# RB1_v2.net
KiCad netlist of a schematic drawn in EAGLE
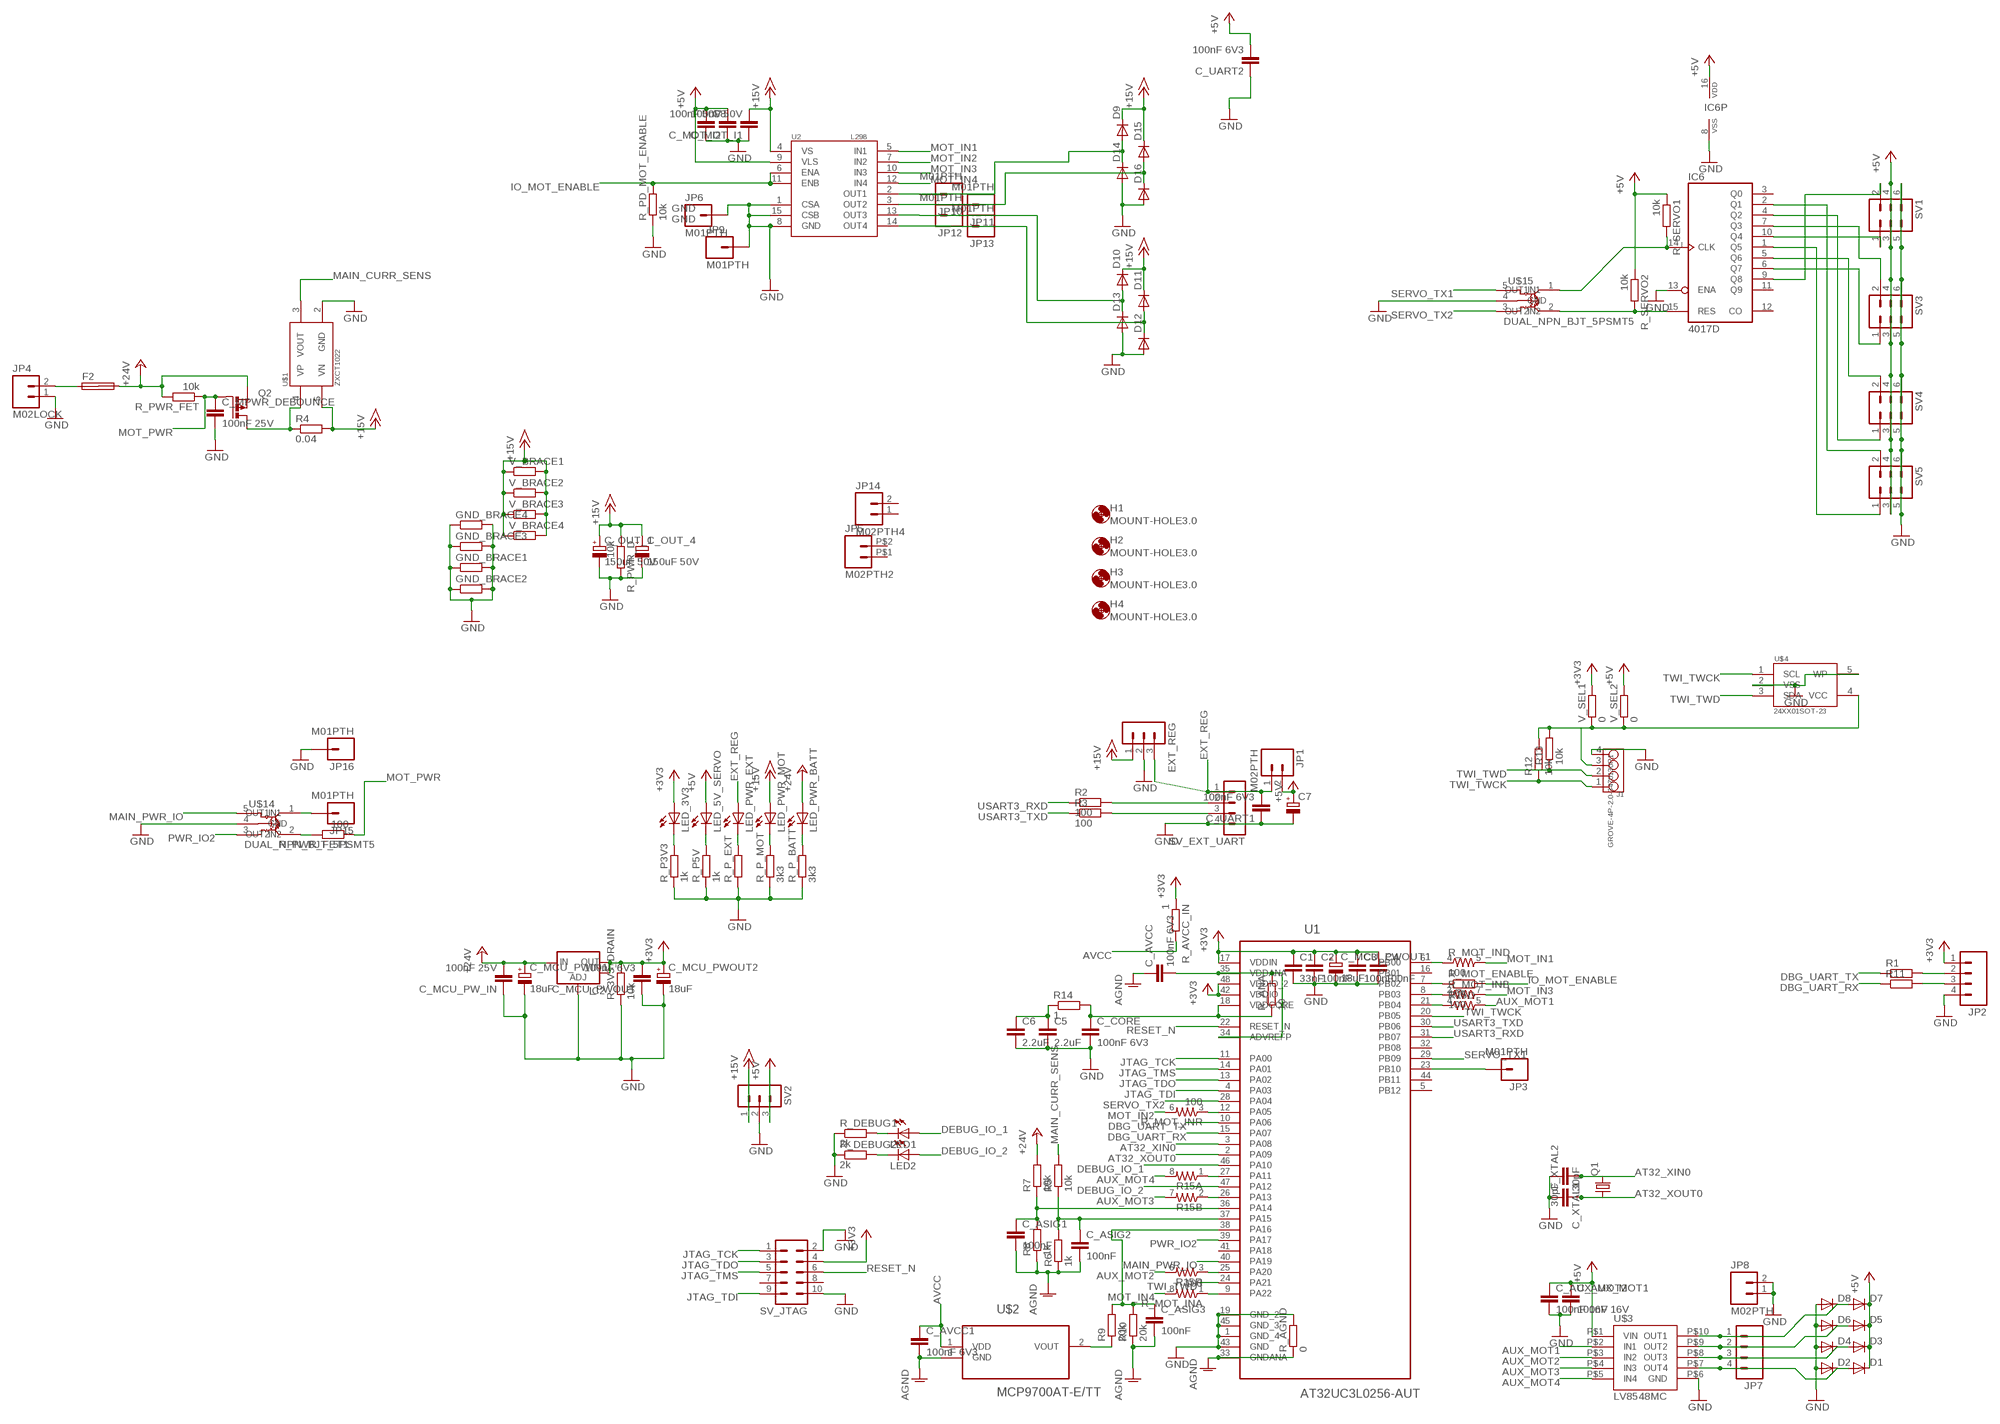
[diagram p0: schematic, sheet 1]

(export (version "E")
  (design (tool "Eeschema 10.0.6"))
  (components
    (comp (ref "C1")
      (value "33nF")
      (footprint "eagle-import:C0603K")
      (libsource (lib "eagle-import") (part "C-EUC0603K"))
    )
    (comp (ref "C2")
      (value "100nF")
      (footprint "eagle-import:C0603K")
      (libsource (lib "eagle-import") (part "C-EUC0603K"))
    )
    (comp (ref "C3")
      (value "100nF")
      (footprint "eagle-import:C0603K")
      (libsource (lib "eagle-import") (part "C-EUC0603K"))
    )
    (comp (ref "C4")
      (value "100nF")
      (footprint "eagle-import:C0603K")
      (libsource (lib "eagle-import") (part "C-EUC0603K"))
    )
    (comp (ref "C5")
      (value "2.2uF")
      (footprint "eagle-import:C0603K")
      (libsource (lib "eagle-import") (part "C-EUC0603K"))
    )
    (comp (ref "C6")
      (value "2.2uF")
      (footprint "eagle-import:C0603K")
      (libsource (lib "eagle-import") (part "C-EUC0603K"))
    )
    (comp (ref "C7")
      (value "CPOL-EU153CLV-0807")
      (footprint "eagle-import:153CLV-0807")
      (libsource (lib "eagle-import") (part "CPOL-EU153CLV-0807"))
    )
    (comp (ref "C8")
      (value "C-EUC1210K")
      (footprint "eagle-import:C1210K")
      (libsource (lib "eagle-import") (part "C-EUC1210K"))
    )
    (comp (ref "C_ASIG1")
      (value "100nF")
      (footprint "eagle-import:C0603K")
      (libsource (lib "eagle-import") (part "C-EUC0603K"))
    )
    (comp (ref "C_ASIG2")
      (value "100nF")
      (footprint "eagle-import:C0603K")
      (libsource (lib "eagle-import") (part "C-EUC0603K"))
    )
    (comp (ref "C_ASIG3")
      (value "100nF")
      (footprint "eagle-import:C0603K")
      (libsource (lib "eagle-import") (part "C-EUC0603K"))
    )
    (comp (ref "C_AUX_MOT1")
      (value "100nF 16V")
      (footprint "eagle-import:C0603K")
      (libsource (lib "eagle-import") (part "C-EUC0603K"))
    )
    (comp (ref "C_AUX_MOT2")
      (value "100nF 16V")
      (footprint "eagle-import:C0603K")
      (libsource (lib "eagle-import") (part "C-EUC0603K"))
    )
    (comp (ref "C_AVCC")
      (value "100nF 6V3")
      (footprint "eagle-import:C0603K")
      (libsource (lib "eagle-import") (part "C-EUC0603K"))
    )
    (comp (ref "C_AVCC1")
      (value "100nF 6V3")
      (footprint "eagle-import:C0603K")
      (libsource (lib "eagle-import") (part "C-EUC0603K"))
    )
    (comp (ref "C_CORE")
      (value "100nF 6V3")
      (footprint "eagle-import:C0603K")
      (libsource (lib "eagle-import") (part "C-EUC0603K"))
    )
    (comp (ref "C_MCU_PWIN1")
      (value "18uF")
      (footprint "eagle-import:E2-5")
      (libsource (lib "eagle-import") (part "CPOL-EUE2-5"))
    )
    (comp (ref "C_MCU_PWOUT")
      (value "100nF 6V3")
      (footprint "eagle-import:C0603K")
      (libsource (lib "eagle-import") (part "C-EUC0603K"))
    )
    (comp (ref "C_MCU_PWOUT1")
      (value "18uF")
      (footprint "eagle-import:E2-5")
      (libsource (lib "eagle-import") (part "CPOL-EUE2-5"))
    )
    (comp (ref "C_MCU_PWOUT2")
      (value "18uF")
      (footprint "eagle-import:E2-5")
      (libsource (lib "eagle-import") (part "CPOL-EUE2-5"))
    )
    (comp (ref "C_MCU_PW_IN")
      (value "100nF 25V")
      (footprint "eagle-import:C0603K")
      (libsource (lib "eagle-import") (part "C-EUC0603K"))
    )
    (comp (ref "C_MOT_I1")
      (value "100nF 50V")
      (footprint "eagle-import:C0603K")
      (libsource (lib "eagle-import") (part "C-EUC0603K"))
    )
    (comp (ref "C_MOT_I2")
      (value "100nF 50V")
      (footprint "eagle-import:C0603K")
      (libsource (lib "eagle-import") (part "C-EUC0603K"))
    )
    (comp (ref "C_MPWR_DEBOUNCE")
      (value "100nF 25V")
      (footprint "eagle-import:C0603K")
      (libsource (lib "eagle-import") (part "C-EUC0603K"))
    )
    (comp (ref "C_OUT_1")
      (value "150uF 50V")
      (footprint "eagle-import:E5-10,5")
      (libsource (lib "eagle-import") (part "CPOL-EUE5-10.5"))
    )
    (comp (ref "C_OUT_4")
      (value "150uF 50V")
      (footprint "eagle-import:E5-10,5")
      (libsource (lib "eagle-import") (part "CPOL-EUE5-10.5"))
    )
    (comp (ref "C_UART1")
      (value "100nF 6V3")
      (footprint "eagle-import:C0603K")
      (libsource (lib "eagle-import") (part "C-EUC0603K"))
    )
    (comp (ref "C_UART2")
      (value "100nF 6V3")
      (footprint "eagle-import:C0603K")
      (libsource (lib "eagle-import") (part "C-EUC0603K"))
    )
    (comp (ref "C_XTAL1")
      (value "30pF")
      (footprint "eagle-import:C0603K")
      (libsource (lib "eagle-import") (part "C-EUC0603K"))
    )
    (comp (ref "C_XTAL2")
      (value "30pF")
      (footprint "eagle-import:C0603K")
      (libsource (lib "eagle-import") (part "C-EUC0603K"))
    )
    (comp (ref "D1")
      (value "DIODE-SOD123")
      (footprint "eagle-import:SOD123")
      (libsource (lib "eagle-import") (part "DIODE-SOD123"))
    )
    (comp (ref "D2")
      (value "DIODE-SOD123")
      (footprint "eagle-import:SOD123")
      (libsource (lib "eagle-import") (part "DIODE-SOD123"))
    )
    (comp (ref "D3")
      (value "DIODE-SOD123")
      (footprint "eagle-import:SOD123")
      (libsource (lib "eagle-import") (part "DIODE-SOD123"))
    )
    (comp (ref "D4")
      (value "DIODE-SOD123")
      (footprint "eagle-import:SOD123")
      (libsource (lib "eagle-import") (part "DIODE-SOD123"))
    )
    (comp (ref "D5")
      (value "DIODE-SOD123")
      (footprint "eagle-import:SOD123")
      (libsource (lib "eagle-import") (part "DIODE-SOD123"))
    )
    (comp (ref "D6")
      (value "DIODE-SOD123")
      (footprint "eagle-import:SOD123")
      (libsource (lib "eagle-import") (part "DIODE-SOD123"))
    )
    (comp (ref "D7")
      (value "DIODE-SOD123")
      (footprint "eagle-import:SOD123")
      (libsource (lib "eagle-import") (part "DIODE-SOD123"))
    )
    (comp (ref "D8")
      (value "DIODE-SOD123")
      (footprint "eagle-import:SOD123")
      (libsource (lib "eagle-import") (part "DIODE-SOD123"))
    )
    (comp (ref "D9")
      (value "DIODE-SOD123")
      (footprint "eagle-import:SOD123")
      (libsource (lib "eagle-import") (part "DIODE-SOD123"))
    )
    (comp (ref "D10")
      (value "DIODE-SOD123")
      (footprint "eagle-import:SOD123")
      (libsource (lib "eagle-import") (part "DIODE-SOD123"))
    )
    (comp (ref "D11")
      (value "DIODE-SOD123")
      (footprint "eagle-import:SOD123")
      (libsource (lib "eagle-import") (part "DIODE-SOD123"))
    )
    (comp (ref "D12")
      (value "DIODE-SOD123")
      (footprint "eagle-import:SOD123")
      (libsource (lib "eagle-import") (part "DIODE-SOD123"))
    )
    (comp (ref "D13")
      (value "DIODE-SOD123")
      (footprint "eagle-import:SOD123")
      (libsource (lib "eagle-import") (part "DIODE-SOD123"))
    )
    (comp (ref "D14")
      (value "DIODE-SOD123")
      (footprint "eagle-import:SOD123")
      (libsource (lib "eagle-import") (part "DIODE-SOD123"))
    )
    (comp (ref "D15")
      (value "DIODE-SOD123")
      (footprint "eagle-import:SOD123")
      (libsource (lib "eagle-import") (part "DIODE-SOD123"))
    )
    (comp (ref "D16")
      (value "DIODE-SOD123")
      (footprint "eagle-import:SOD123")
      (libsource (lib "eagle-import") (part "DIODE-SOD123"))
    )
    (comp (ref "EXT_REG")
      (value "MA03-1")
      (footprint "eagle-import:MA03-1")
      (libsource (lib "eagle-import") (part "MA03-1"))
    )
    (comp (ref "F2")
      (value "SHK20Q")
      (footprint "eagle-import:SHK20Q")
      (libsource (lib "eagle-import") (part "SHK20Q"))
    )
    (comp (ref "GND_BRACE1")
      (value "R-EU_0204/2V")
      (footprint "eagle-import:0204V")
      (libsource (lib "eagle-import") (part "R-EU_0204/2V"))
    )
    (comp (ref "GND_BRACE2")
      (value "R-EU_0204/2V")
      (footprint "eagle-import:0204V")
      (libsource (lib "eagle-import") (part "R-EU_0204/2V"))
    )
    (comp (ref "GND_BRACE3")
      (value "R-EU_0204/2V")
      (footprint "eagle-import:0204V")
      (libsource (lib "eagle-import") (part "R-EU_0204/2V"))
    )
    (comp (ref "GND_BRACE4")
      (value "R-EU_0204/2V")
      (footprint "eagle-import:0204V")
      (libsource (lib "eagle-import") (part "R-EU_0204/2V"))
    )
    (comp (ref "H1")
      (value "MOUNT-HOLE3.0")
      (footprint "eagle-import:3,0")
      (libsource (lib "eagle-import") (part "MOUNT-HOLE3.0"))
    )
    (comp (ref "H2")
      (value "MOUNT-HOLE3.0")
      (footprint "eagle-import:3,0")
      (libsource (lib "eagle-import") (part "MOUNT-HOLE3.0"))
    )
    (comp (ref "H3")
      (value "MOUNT-HOLE3.0")
      (footprint "eagle-import:3,0")
      (libsource (lib "eagle-import") (part "MOUNT-HOLE3.0"))
    )
    (comp (ref "H4")
      (value "MOUNT-HOLE3.0")
      (footprint "eagle-import:3,0")
      (libsource (lib "eagle-import") (part "MOUNT-HOLE3.0"))
    )
    (comp (ref "IC2")
      (value "V_REG_LM1117SOT223")
      (footprint "eagle-import:SOT223")
      (libsource (lib "eagle-import") (part "V_REG_LM1117SOT223"))
    )
    (comp (ref "IC6")
      (value "4017D")
      (footprint "eagle-import:SO16")
      (libsource (lib "eagle-import") (part "4017D"))
    )
    (comp (ref "J1")
      (value "GROVE-4P-2.0-3470130P1")
      (footprint "eagle-import:4P-2.0")
      (libsource (lib "eagle-import") (part "GROVE-4P-2.0-3470130P1"))
    )
    (comp (ref "JP1")
      (value "M02PTH")
      (footprint "eagle-import:1X02")
      (libsource (lib "eagle-import") (part "M02PTH"))
    )
    (comp (ref "JP2")
      (value "M04PTH")
      (footprint "eagle-import:1X04")
      (libsource (lib "eagle-import") (part "M04PTH"))
    )
    (comp (ref "JP3")
      (value "M01PTH")
      (footprint "eagle-import:1X01")
      (libsource (lib "eagle-import") (part "M01PTH"))
    )
    (comp (ref "JP4")
      (value "M02LOCK")
      (footprint "eagle-import:1X02_LOCK")
      (libsource (lib "eagle-import") (part "M02LOCK"))
    )
    (comp (ref "JP5")
      (value "M02PTH2")
      (footprint "eagle-import:1X02_BIG")
      (libsource (lib "eagle-import") (part "M02PTH2"))
    )
    (comp (ref "JP6")
      (value "M01PTH")
      (footprint "eagle-import:1X01")
      (libsource (lib "eagle-import") (part "M01PTH"))
    )
    (comp (ref "JP7")
      (value "M04PTH")
      (footprint "eagle-import:1X04")
      (libsource (lib "eagle-import") (part "M04PTH"))
    )
    (comp (ref "JP8")
      (value "M02PTH")
      (footprint "eagle-import:1X02")
      (libsource (lib "eagle-import") (part "M02PTH"))
    )
    (comp (ref "JP9")
      (value "M01PTH")
      (footprint "eagle-import:1X01")
      (libsource (lib "eagle-import") (part "M01PTH"))
    )
    (comp (ref "JP10")
      (value "M01PTH")
      (footprint "eagle-import:1X01")
      (libsource (lib "eagle-import") (part "M01PTH"))
    )
    (comp (ref "JP11")
      (value "M01PTH")
      (footprint "eagle-import:1X01")
      (libsource (lib "eagle-import") (part "M01PTH"))
    )
    (comp (ref "JP12")
      (value "M01PTH")
      (footprint "eagle-import:1X01")
      (libsource (lib "eagle-import") (part "M01PTH"))
    )
    (comp (ref "JP13")
      (value "M01PTH")
      (footprint "eagle-import:1X01")
      (libsource (lib "eagle-import") (part "M01PTH"))
    )
    (comp (ref "JP14")
      (value "M02PTH4")
      (footprint "eagle-import:1X02_XTRA_BIG")
      (libsource (lib "eagle-import") (part "M02PTH4"))
    )
    (comp (ref "JP15")
      (value "M01PTH")
      (footprint "eagle-import:1X01")
      (libsource (lib "eagle-import") (part "M01PTH"))
    )
    (comp (ref "JP16")
      (value "M01PTH")
      (footprint "eagle-import:1X01")
      (libsource (lib "eagle-import") (part "M01PTH"))
    )
    (comp (ref "LED1")
      (value "LEDCHIPLED_0603")
      (footprint "eagle-import:CHIPLED_0603")
      (libsource (lib "eagle-import") (part "LEDCHIPLED_0603"))
    )
    (comp (ref "LED2")
      (value "LEDCHIPLED_0603")
      (footprint "eagle-import:CHIPLED_0603")
      (libsource (lib "eagle-import") (part "LEDCHIPLED_0603"))
    )
    (comp (ref "LED_3V3")
      (value "LEDSML0603")
      (footprint "eagle-import:SML0603")
      (libsource (lib "eagle-import") (part "LEDSML0603"))
    )
    (comp (ref "LED_5V_SERVO")
      (value "LEDSML0603")
      (footprint "eagle-import:SML0603")
      (libsource (lib "eagle-import") (part "LEDSML0603"))
    )
    (comp (ref "LED_PWR_BATT")
      (value "LEDSML0603")
      (footprint "eagle-import:SML0603")
      (libsource (lib "eagle-import") (part "LEDSML0603"))
    )
    (comp (ref "LED_PWR_EXT")
      (value "LEDSML0603")
      (footprint "eagle-import:SML0603")
      (libsource (lib "eagle-import") (part "LEDSML0603"))
    )
    (comp (ref "LED_PWR_MOT")
      (value "LEDSML0603")
      (footprint "eagle-import:SML0603")
      (libsource (lib "eagle-import") (part "LEDSML0603"))
    )
    (comp (ref "Q1")
      (value "CRYSTALHC49S")
      (footprint "eagle-import:HC49_S")
      (libsource (lib "eagle-import") (part "CRYSTALHC49S"))
    )
    (comp (ref "Q2")
      (value "P-MOSFET-SO8")
      (footprint "eagle-import:SO-08")
      (libsource (lib "eagle-import") (part "P-MOSFET-SO8"))
    )
    (comp (ref "R1")
      (value "R-EU_R0603")
      (footprint "eagle-import:R0603")
      (libsource (lib "eagle-import") (part "R-EU_R0603"))
    )
    (comp (ref "R2")
      (value "100")
      (footprint "eagle-import:R0603")
      (libsource (lib "eagle-import") (part "R-EU_R0603"))
    )
    (comp (ref "R3")
      (value "100")
      (footprint "eagle-import:R0603")
      (libsource (lib "eagle-import") (part "R-EU_R0603"))
    )
    (comp (ref "R4")
      (value "0.04")
      (footprint "eagle-import:0617_17")
      (libsource (lib "eagle-import") (part "R-EU_0617/17"))
    )
    (comp (ref "R5")
      (value "10k")
      (footprint "eagle-import:R0603")
      (libsource (lib "eagle-import") (part "R-EU_R0603"))
    )
    (comp (ref "R6")
      (value "1k")
      (footprint "eagle-import:R0603")
      (libsource (lib "eagle-import") (part "R-EU_R0603"))
    )
    (comp (ref "R7")
      (value "10k")
      (footprint "eagle-import:R0603")
      (libsource (lib "eagle-import") (part "R-EU_R0603"))
    )
    (comp (ref "R8")
      (value "1k")
      (footprint "eagle-import:R0603")
      (libsource (lib "eagle-import") (part "R-EU_R0603"))
    )
    (comp (ref "R9")
      (value "20k")
      (footprint "eagle-import:R0603")
      (libsource (lib "eagle-import") (part "R-EU_R0603"))
    )
    (comp (ref "R10")
      (value "20k")
      (footprint "eagle-import:R0603")
      (libsource (lib "eagle-import") (part "R-EU_R0603"))
    )
    (comp (ref "R11")
      (value "R-EU_R0603")
      (footprint "eagle-import:R0603")
      (libsource (lib "eagle-import") (part "R-EU_R0603"))
    )
    (comp (ref "R12")
      (value "10k")
      (footprint "eagle-import:R0603")
      (libsource (lib "eagle-import") (part "R-EU_R0603"))
    )
    (comp (ref "R13")
      (value "10k")
      (footprint "eagle-import:R0603")
      (libsource (lib "eagle-import") (part "R-EU_R0603"))
    )
    (comp (ref "R14")
      (value "1")
      (footprint "eagle-import:R0603")
      (libsource (lib "eagle-import") (part "R-EU_R0603"))
    )
    (comp (ref "R15")
      (value "RESISTOR-ARRAY0603-ARV")
      (footprint "eagle-import:0603-ARV")
      (libsource (lib "eagle-import") (part "RESISTOR-ARRAY0603-ARV"))
    )
    (comp (ref "R_3V3_DRAIN")
      (value "10k")
      (footprint "eagle-import:R0603")
      (libsource (lib "eagle-import") (part "R-EU_R0603"))
    )
    (comp (ref "R_AGND")
      (value "0")
      (footprint "eagle-import:R0603")
      (libsource (lib "eagle-import") (part "R-EU_R0603"))
    )
    (comp (ref "R_ANA")
      (value "10")
      (footprint "eagle-import:R0603")
      (libsource (lib "eagle-import") (part "R-EU_R0603"))
    )
    (comp (ref "R_AVCC_IN")
      (value "1")
      (footprint "eagle-import:R0603")
      (libsource (lib "eagle-import") (part "R-EU_R0603"))
    )
    (comp (ref "R_DEBUG1")
      (value "2k")
      (footprint "eagle-import:R0603")
      (libsource (lib "eagle-import") (part "R-EU_R0603"))
    )
    (comp (ref "R_DEBUG2")
      (value "2k")
      (footprint "eagle-import:R0603")
      (libsource (lib "eagle-import") (part "R-EU_R0603"))
    )
    (comp (ref "R_MOT_ENABLE")
      (value "100")
      (footprint "eagle-import:R0603")
      (libsource (lib "eagle-import") (part "R-EU_R0603"))
    )
    (comp (ref "R_MOT_IN")
      (value "100")
      (footprint "eagle-import:0603-ARV")
      (libsource (lib "eagle-import") (part "RESISTOR-ARRAY0603-ARV"))
    )
    (comp (ref "R_P3V3")
      (value "1k")
      (footprint "eagle-import:R0603")
      (libsource (lib "eagle-import") (part "R-EU_R0603"))
    )
    (comp (ref "R_P5V")
      (value "1k")
      (footprint "eagle-import:R0603")
      (libsource (lib "eagle-import") (part "R-EU_R0603"))
    )
    (comp (ref "R_PD_MOT_ENABLE")
      (value "10k")
      (footprint "eagle-import:R0603")
      (libsource (lib "eagle-import") (part "R-EU_R0603"))
    )
    (comp (ref "R_PWR_D")
      (value "10k")
      (footprint "eagle-import:R0603")
      (libsource (lib "eagle-import") (part "R-EU_R0603"))
    )
    (comp (ref "R_PWR_FET")
      (value "10k")
      (footprint "eagle-import:R0603")
      (libsource (lib "eagle-import") (part "R-EU_R0603"))
    )
    (comp (ref "R_PWR_FET1")
      (value "100")
      (footprint "eagle-import:R0603")
      (libsource (lib "eagle-import") (part "R-EU_R0603"))
    )
    (comp (ref "R_P_BATT")
      (value "3k3")
      (footprint "eagle-import:R0603")
      (libsource (lib "eagle-import") (part "R-EU_R0603"))
    )
    (comp (ref "R_P_EXT")
      (value "R-EU_R0603")
      (footprint "eagle-import:R0603")
      (libsource (lib "eagle-import") (part "R-EU_R0603"))
    )
    (comp (ref "R_P_MOT")
      (value "3k3")
      (footprint "eagle-import:R0603")
      (libsource (lib "eagle-import") (part "R-EU_R0603"))
    )
    (comp (ref "R_SERVO1")
      (value "10k")
      (footprint "eagle-import:R0603")
      (libsource (lib "eagle-import") (part "R-EU_R0603"))
    )
    (comp (ref "R_SERVO2")
      (value "10k")
      (footprint "eagle-import:R0603")
      (libsource (lib "eagle-import") (part "R-EU_R0603"))
    )
    (comp (ref "SV1")
      (value "MA03-2")
      (footprint "eagle-import:MA03-2")
      (libsource (lib "eagle-import") (part "MA03-2"))
    )
    (comp (ref "SV2")
      (value "MA03-1")
      (footprint "eagle-import:MA03-1")
      (libsource (lib "eagle-import") (part "MA03-1"))
    )
    (comp (ref "SV3")
      (value "MA03-2")
      (footprint "eagle-import:MA03-2")
      (libsource (lib "eagle-import") (part "MA03-2"))
    )
    (comp (ref "SV4")
      (value "MA03-2")
      (footprint "eagle-import:MA03-2")
      (libsource (lib "eagle-import") (part "MA03-2"))
    )
    (comp (ref "SV5")
      (value "MA03-2")
      (footprint "eagle-import:MA03-2")
      (libsource (lib "eagle-import") (part "MA03-2"))
    )
    (comp (ref "SV_EXT_UART")
      (value "MA04-1")
      (footprint "eagle-import:MA04-1")
      (libsource (lib "eagle-import") (part "MA04-1"))
    )
    (comp (ref "SV_JTAG")
      (value "MA05-2")
      (footprint "eagle-import:MA05-2")
      (libsource (lib "eagle-import") (part "MA05-2"))
    )
    (comp (ref "U$1")
      (value "ZXCT1022")
      (footprint "eagle-import:SOT23-5")
      (libsource (lib "eagle-import") (part "ZXCT1022"))
    )
    (comp (ref "U$2")
      (value "MCP9700AT-E/TT")
      (footprint "eagle-import:SOT95P237X112-3N")
      (libsource (lib "eagle-import") (part "MCP9700AT-E/TT"))
    )
    (comp (ref "U$3")
      (value "LV8548MC")
      (footprint "eagle-import:SOIC10")
      (libsource (lib "eagle-import") (part "LV8548MC"))
    )
    (comp (ref "U$4")
      (value "24XX01SOT-23")
      (footprint "eagle-import:SOT23-5L")
      (libsource (lib "eagle-import") (part "24XX01SOT-23"))
    )
    (comp (ref "U$14")
      (value "DUAL_NPN_BJT_5PSMT5")
      (footprint "eagle-import:SC-74A")
      (libsource (lib "eagle-import") (part "DUAL_NPN_BJT_5PSMT5"))
    )
    (comp (ref "U$15")
      (value "DUAL_NPN_BJT_5PSMT5")
      (footprint "eagle-import:SC-74A")
      (libsource (lib "eagle-import") (part "DUAL_NPN_BJT_5PSMT5"))
    )
    (comp (ref "U1")
      (value "AT32UC3L0256-AUT")
      (footprint "eagle-import:QFP50P900X900X120-48N")
      (libsource (lib "eagle-import") (part "AT32UC3L0256-AUT"))
    )
    (comp (ref "U2")
      (value "L298")
      (footprint "eagle-import:MULTIWATT15")
      (libsource (lib "eagle-import") (part "L298"))
    )
    (comp (ref "V_BRACE1")
      (value "R-EU_0204/2V")
      (footprint "eagle-import:0204V")
      (libsource (lib "eagle-import") (part "R-EU_0204/2V"))
    )
    (comp (ref "V_BRACE2")
      (value "R-EU_0204/2V")
      (footprint "eagle-import:0204V")
      (libsource (lib "eagle-import") (part "R-EU_0204/2V"))
    )
    (comp (ref "V_BRACE3")
      (value "R-EU_0204/2V")
      (footprint "eagle-import:0204V")
      (libsource (lib "eagle-import") (part "R-EU_0204/2V"))
    )
    (comp (ref "V_BRACE4")
      (value "R-EU_0204/2V")
      (footprint "eagle-import:0204V")
      (libsource (lib "eagle-import") (part "R-EU_0204/2V"))
    )
    (comp (ref "V_SEL1")
      (value "0")
      (footprint "eagle-import:R0603")
      (libsource (lib "eagle-import") (part "R-EU_R0603"))
    )
    (comp (ref "V_SEL2")
      (value "0")
      (footprint "eagle-import:R0603")
      (libsource (lib "eagle-import") (part "R-EU_R0603"))
    )
  )
  (nets
    (net (code "1") (name "+3V3") (class "Default")
      (node (ref "C1") (pin "1") (pinfunction "1_1") (pintype "passive"))
      (node (ref "C2") (pin "1") (pinfunction "1_1") (pintype "passive"))
      (node (ref "C3") (pin "1") (pinfunction "1_1") (pintype "passive"))
      (node (ref "C4") (pin "1") (pinfunction "1_1") (pintype "passive"))
      (node (ref "C_MCU_PWOUT") (pin "2") (pinfunction "2_2") (pintype "passive"))
      (node (ref "C_MCU_PWOUT1") (pin "+") (pinfunction "+_+") (pintype "passive"))
      (node (ref "C_MCU_PWOUT2") (pin "+") (pinfunction "+_+") (pintype "passive"))
      (node (ref "IC2") (pin "2") (pinfunction "OUT_2") (pintype "output"))
      (node (ref "IC2") (pin "4") (pinfunction "OUT_4") (pintype "output"))
      (node (ref "JP2") (pin "1") (pinfunction "1_1") (pintype "passive"))
      (node (ref "LED_3V3") (pin "A") (pinfunction "A_A") (pintype "passive"))
      (node (ref "R_3V3_DRAIN") (pin "2") (pinfunction "2_2") (pintype "passive"))
      (node (ref "R_AVCC_IN") (pin "1") (pinfunction "1_1") (pintype "passive"))
      (node (ref "SV_JTAG") (pin "4") (pinfunction "4_4") (pintype "passive"))
      (node (ref "U1") (pin "17") (pinfunction "VDDIN_17") (pintype "power_in"))
      (node (ref "U1") (pin "42") (pinfunction "VDDIO_42") (pintype "power_in"))
      (node (ref "U1") (pin "48") (pinfunction "VDDIO_2_48") (pintype "power_in"))
      (node (ref "V_SEL1") (pin "2") (pinfunction "2_2") (pintype "passive"))
    )
    (net (code "2") (name "+5V") (class "Default")
      (node (ref "C7") (pin "+") (pinfunction "+_+") (pintype "passive"))
      (node (ref "C8") (pin "1") (pinfunction "1_1") (pintype "passive"))
      (node (ref "C_AUX_MOT1") (pin "1") (pinfunction "1_1") (pintype "passive"))
      (node (ref "C_AUX_MOT2") (pin "1") (pinfunction "1_1") (pintype "passive"))
      (node (ref "C_MOT_I2") (pin "2") (pinfunction "2_2") (pintype "passive"))
      (node (ref "C_UART2") (pin "2") (pinfunction "2_2") (pintype "passive"))
      (node (ref "D1") (pin "C") (pinfunction "C_C") (pintype "passive"))
      (node (ref "D3") (pin "C") (pinfunction "C_C") (pintype "passive"))
      (node (ref "D5") (pin "C") (pinfunction "C_C") (pintype "passive"))
      (node (ref "D7") (pin "C") (pinfunction "C_C") (pintype "passive"))
      (node (ref "IC6") (pin "16") (pinfunction "VDD_16") (pintype "power_in"))
      (node (ref "JP1") (pin "2") (pinfunction "2_2") (pintype "passive"))
      (node (ref "LED_5V_SERVO") (pin "A") (pinfunction "A_A") (pintype "passive"))
      (node (ref "R_SERVO1") (pin "1") (pinfunction "1_1") (pintype "passive"))
      (node (ref "R_SERVO2") (pin "1") (pinfunction "1_1") (pintype "passive"))
      (node (ref "SV1") (pin "3") (pinfunction "3_3") (pintype "passive"))
      (node (ref "SV1") (pin "4") (pinfunction "4_4") (pintype "passive"))
      (node (ref "SV2") (pin "3") (pinfunction "3_3") (pintype "passive"))
      (node (ref "SV3") (pin "3") (pinfunction "3_3") (pintype "passive"))
      (node (ref "SV3") (pin "4") (pinfunction "4_4") (pintype "passive"))
      (node (ref "SV4") (pin "3") (pinfunction "3_3") (pintype "passive"))
      (node (ref "SV4") (pin "4") (pinfunction "4_4") (pintype "passive"))
      (node (ref "SV5") (pin "3") (pinfunction "3_3") (pintype "passive"))
      (node (ref "SV5") (pin "4") (pinfunction "4_4") (pintype "passive"))
      (node (ref "U$3") (pin "P$1") (pinfunction "VIN_P$1") (pintype "bidirectional"))
      (node (ref "U2") (pin "9") (pinfunction "VLS_9") (pintype "bidirectional"))
      (node (ref "V_SEL2") (pin "2") (pinfunction "2_2") (pintype "passive"))
    )
    (net (code "3") (name "+15V") (class "Default")
      (node (ref "C_MOT_I1") (pin "2") (pinfunction "2_2") (pintype "passive"))
      (node (ref "C_OUT_1") (pin "+") (pinfunction "+_+") (pintype "passive"))
      (node (ref "C_OUT_4") (pin "+") (pinfunction "+_+") (pintype "passive"))
      (node (ref "D10") (pin "C") (pinfunction "C_C") (pintype "passive"))
      (node (ref "D11") (pin "C") (pinfunction "C_C") (pintype "passive"))
      (node (ref "D15") (pin "C") (pinfunction "C_C") (pintype "passive"))
      (node (ref "D9") (pin "C") (pinfunction "C_C") (pintype "passive"))
      (node (ref "EXT_REG") (pin "1") (pinfunction "1_1") (pintype "passive"))
      (node (ref "LED_PWR_MOT") (pin "A") (pinfunction "A_A") (pintype "passive"))
      (node (ref "R4") (pin "2") (pinfunction "2_2") (pintype "passive"))
      (node (ref "R_PWR_D") (pin "1") (pinfunction "1_1") (pintype "passive"))
      (node (ref "SV2") (pin "1") (pinfunction "1_1") (pintype "passive"))
      (node (ref "U$1") (pin "5") (pinfunction "VN_5") (pintype "bidirectional"))
      (node (ref "U2") (pin "4") (pinfunction "VS_4") (pintype "bidirectional"))
      (node (ref "V_BRACE1") (pin "1") (pinfunction "1_1") (pintype "passive"))
      (node (ref "V_BRACE1") (pin "2") (pinfunction "2_2") (pintype "passive"))
      (node (ref "V_BRACE2") (pin "1") (pinfunction "1_1") (pintype "passive"))
      (node (ref "V_BRACE2") (pin "2") (pinfunction "2_2") (pintype "passive"))
      (node (ref "V_BRACE3") (pin "1") (pinfunction "1_1") (pintype "passive"))
      (node (ref "V_BRACE3") (pin "2") (pinfunction "2_2") (pintype "passive"))
      (node (ref "V_BRACE4") (pin "1") (pinfunction "1_1") (pintype "passive"))
      (node (ref "V_BRACE4") (pin "2") (pinfunction "2_2") (pintype "passive"))
    )
    (net (code "4") (name "+24V") (class "Default")
      (node (ref "C_MCU_PWIN1") (pin "+") (pinfunction "+_+") (pintype "passive"))
      (node (ref "C_MCU_PW_IN") (pin "2") (pinfunction "2_2") (pintype "passive"))
      (node (ref "F2") (pin "2A") (pinfunction "2A_2A") (pintype "passive"))
      (node (ref "IC2") (pin "3") (pinfunction "IN_3") (pintype "input"))
      (node (ref "LED_PWR_BATT") (pin "A") (pinfunction "A_A") (pintype "passive"))
      (node (ref "Q2") (pin "1") (pinfunction "S_1") (pintype "passive"))
      (node (ref "Q2") (pin "2") (pinfunction "S_2") (pintype "passive"))
      (node (ref "Q2") (pin "3") (pinfunction "S_3") (pintype "passive"))
      (node (ref "R7") (pin "2") (pinfunction "2_2") (pintype "passive"))
      (node (ref "R_PWR_FET") (pin "2") (pinfunction "2_2") (pintype "passive"))
    )
    (net (code "5") (name "/AT32_XIN0") (class "Default")
      (node (ref "C_XTAL1") (pin "1") (pinfunction "1_1") (pintype "passive"))
      (node (ref "Q1") (pin "2") (pinfunction "2_2") (pintype "passive"))
      (node (ref "U1") (pin "3") (pinfunction "PA08_3") (pintype "bidirectional"))
    )
    (net (code "6") (name "/AT32_XOUT0") (class "Default")
      (node (ref "C_XTAL2") (pin "2") (pinfunction "2_2") (pintype "passive"))
      (node (ref "Q1") (pin "1") (pinfunction "1_1") (pintype "passive"))
      (node (ref "U1") (pin "2") (pinfunction "PA09_2") (pintype "bidirectional"))
    )
    (net (code "7") (name "/AUX_MOT1") (class "Default")
      (node (ref "R15") (pin "5") (pinfunction "2_5") (pintype "passive"))
      (node (ref "U$3") (pin "P$2") (pinfunction "IN1_P$2") (pintype "bidirectional"))
    )
    (net (code "8") (name "/AUX_MOT2") (class "Default")
      (node (ref "R15") (pin "6") (pinfunction "2_6") (pintype "passive"))
      (node (ref "U$3") (pin "P$3") (pinfunction "IN2_P$3") (pintype "bidirectional"))
    )
    (net (code "9") (name "/AUX_MOT3") (class "Default")
      (node (ref "R15") (pin "7") (pinfunction "2_7") (pintype "passive"))
      (node (ref "U$3") (pin "P$4") (pinfunction "IN3_P$4") (pintype "bidirectional"))
    )
    (net (code "10") (name "/AUX_MOT4") (class "Default")
      (node (ref "R15") (pin "8") (pinfunction "2_8") (pintype "passive"))
      (node (ref "U$3") (pin "P$5") (pinfunction "IN4_P$5") (pintype "bidirectional"))
    )
    (net (code "11") (name "/AVCC") (class "Default")
      (node (ref "C_AVCC1") (pin "1") (pinfunction "1_1") (pintype "passive"))
      (node (ref "R_AVCC_IN") (pin "2") (pinfunction "2_2") (pintype "passive"))
      (node (ref "U$2") (pin "1") (pinfunction "VDD_1") (pintype "power_in"))
    )
    (net (code "12") (name "/DBG_UART_RX") (class "Default")
      (node (ref "R11") (pin "1") (pinfunction "1_1") (pintype "passive"))
      (node (ref "U1") (pin "15") (pinfunction "PA07_15") (pintype "bidirectional"))
    )
    (net (code "13") (name "/DBG_UART_TX") (class "Default")
      (node (ref "R1") (pin "1") (pinfunction "1_1") (pintype "passive"))
      (node (ref "U1") (pin "10") (pinfunction "PA06_10") (pintype "bidirectional"))
    )
    (net (code "14") (name "/DEBUG_IO_1") (class "Default")
      (node (ref "LED1") (pin "A") (pinfunction "A_A") (pintype "passive"))
      (node (ref "U1") (pin "46") (pinfunction "PA10_46") (pintype "bidirectional"))
    )
    (net (code "15") (name "/DEBUG_IO_2") (class "Default")
      (node (ref "LED2") (pin "A") (pinfunction "A_A") (pintype "passive"))
      (node (ref "U1") (pin "47") (pinfunction "PA12_47") (pintype "bidirectional"))
    )
    (net (code "16") (name "/EXT_REG") (class "Default")
      (node (ref "C_UART1") (pin "2") (pinfunction "2_2") (pintype "passive"))
      (node (ref "EXT_REG") (pin "3") (pinfunction "3_3") (pintype "passive"))
      (node (ref "JP1") (pin "1") (pinfunction "1_1") (pintype "passive"))
      (node (ref "LED_PWR_EXT") (pin "A") (pinfunction "A_A") (pintype "passive"))
      (node (ref "SV_EXT_UART") (pin "1") (pinfunction "1_1") (pintype "passive"))
    )
    (net (code "17") (name "/IO_MOT_ENABLE") (class "Default")
      (node (ref "R_MOT_ENABLE") (pin "2") (pinfunction "2_2") (pintype "passive"))
      (node (ref "R_PD_MOT_ENABLE") (pin "2") (pinfunction "2_2") (pintype "passive"))
      (node (ref "U2") (pin "11") (pinfunction "ENB_11") (pintype "bidirectional"))
      (node (ref "U2") (pin "6") (pinfunction "ENA_6") (pintype "bidirectional"))
    )
    (net (code "18") (name "/JTAG_TCK") (class "Default")
      (node (ref "SV_JTAG") (pin "1") (pinfunction "1_1") (pintype "passive"))
      (node (ref "U1") (pin "11") (pinfunction "PA00_11") (pintype "bidirectional"))
    )
    (net (code "19") (name "/JTAG_TDI") (class "Default")
      (node (ref "SV_JTAG") (pin "9") (pinfunction "9_9") (pintype "passive"))
      (node (ref "U1") (pin "4") (pinfunction "PA03_4") (pintype "bidirectional"))
    )
    (net (code "20") (name "/JTAG_TDO") (class "Default")
      (node (ref "SV_JTAG") (pin "3") (pinfunction "3_3") (pintype "passive"))
      (node (ref "U1") (pin "13") (pinfunction "PA02_13") (pintype "bidirectional"))
    )
    (net (code "21") (name "/JTAG_TMS") (class "Default")
      (node (ref "SV_JTAG") (pin "5") (pinfunction "5_5") (pintype "passive"))
      (node (ref "U1") (pin "14") (pinfunction "PA01_14") (pintype "bidirectional"))
    )
    (net (code "22") (name "/MAIN_CURR_SENS") (class "Default")
      (node (ref "R5") (pin "2") (pinfunction "2_2") (pintype "passive"))
      (node (ref "U$1") (pin "3") (pinfunction "VOUT_3") (pintype "bidirectional"))
    )
    (net (code "23") (name "/MAIN_PWR_IO") (class "Default")
      (node (ref "U$14") (pin "5") (pinfunction "IN1_5") (pintype "bidirectional"))
      (node (ref "U1") (pin "40") (pinfunction "PA19_40") (pintype "bidirectional"))
    )
    (net (code "24") (name "/MOT_IN1") (class "Default")
      (node (ref "R_MOT_IN") (pin "5") (pinfunction "2_5") (pintype "passive"))
      (node (ref "U2") (pin "5") (pinfunction "IN1_5") (pintype "bidirectional"))
    )
    (net (code "25") (name "/MOT_IN2") (class "Default")
      (node (ref "R_MOT_IN") (pin "6") (pinfunction "2_6") (pintype "passive"))
      (node (ref "U2") (pin "7") (pinfunction "IN2_7") (pintype "bidirectional"))
    )
    (net (code "26") (name "/MOT_IN3") (class "Default")
      (node (ref "R_MOT_IN") (pin "7") (pinfunction "2_7") (pintype "passive"))
      (node (ref "U2") (pin "10") (pinfunction "IN3_10") (pintype "bidirectional"))
    )
    (net (code "27") (name "/MOT_IN4") (class "Default")
      (node (ref "R_MOT_IN") (pin "8") (pinfunction "2_8") (pintype "passive"))
      (node (ref "U2") (pin "12") (pinfunction "IN4_12") (pintype "bidirectional"))
    )
    (net (code "28") (name "/MOT_PWR") (class "Default")
      (node (ref "C_MPWR_DEBOUNCE") (pin "1") (pinfunction "1_1") (pintype "passive"))
      (node (ref "Q2") (pin "4") (pinfunction "G_4") (pintype "passive"))
      (node (ref "R_PWR_FET") (pin "1") (pinfunction "1_1") (pintype "passive"))
      (node (ref "R_PWR_FET1") (pin "1") (pinfunction "1_1") (pintype "passive"))
    )
    (net (code "29") (name "/PWR_IO2") (class "Default")
      (node (ref "U$14") (pin "3") (pinfunction "IN2_3") (pintype "bidirectional"))
      (node (ref "U1") (pin "39") (pinfunction "PA17_39") (pintype "bidirectional"))
    )
    (net (code "30") (name "/RESET_N") (class "Default")
      (node (ref "SV_JTAG") (pin "6") (pinfunction "6_6") (pintype "passive"))
      (node (ref "U1") (pin "22") (pinfunction "RESET_N_22") (pintype "input"))
    )
    (net (code "31") (name "/SERVO_TX1") (class "Default")
      (node (ref "U$15") (pin "5") (pinfunction "IN1_5") (pintype "bidirectional"))
      (node (ref "U1") (pin "29") (pinfunction "PB09_29") (pintype "bidirectional"))
    )
    (net (code "32") (name "/SERVO_TX2") (class "Default")
      (node (ref "U$15") (pin "3") (pinfunction "IN2_3") (pintype "bidirectional"))
      (node (ref "U1") (pin "28") (pinfunction "PA04_28") (pintype "bidirectional"))
    )
    (net (code "33") (name "/TWI_TWCK") (class "Default")
      (node (ref "J1") (pin "1") (pinfunction "1_1") (pintype "bidirectional"))
      (node (ref "R12") (pin "1") (pinfunction "1_1") (pintype "passive"))
      (node (ref "U$4") (pin "1") (pinfunction "SCL_1") (pintype "bidirectional"))
      (node (ref "U1") (pin "20") (pinfunction "PB05_20") (pintype "bidirectional"))
    )
    (net (code "34") (name "/TWI_TWD") (class "Default")
      (node (ref "J1") (pin "2") (pinfunction "2_2") (pintype "bidirectional"))
      (node (ref "R13") (pin "1") (pinfunction "1_1") (pintype "passive"))
      (node (ref "U$4") (pin "3") (pinfunction "SDA_3") (pintype "bidirectional"))
      (node (ref "U1") (pin "24") (pinfunction "PA21_24") (pintype "bidirectional"))
    )
    (net (code "35") (name "/USART3_RXD") (class "Default")
      (node (ref "R2") (pin "1") (pinfunction "1_1") (pintype "passive"))
      (node (ref "U1") (pin "31") (pinfunction "PB07_31") (pintype "bidirectional"))
    )
    (net (code "36") (name "/USART3_TXD") (class "Default")
      (node (ref "R3") (pin "1") (pinfunction "1_1") (pintype "passive"))
      (node (ref "U1") (pin "30") (pinfunction "PB06_30") (pintype "bidirectional"))
    )
    (net (code "37") (name "AGND") (class "Default")
      (node (ref "C_ASIG1") (pin "2") (pinfunction "2_2") (pintype "passive"))
      (node (ref "C_ASIG2") (pin "2") (pinfunction "2_2") (pintype "passive"))
      (node (ref "C_ASIG3") (pin "2") (pinfunction "2_2") (pintype "passive"))
      (node (ref "C_AVCC") (pin "1") (pinfunction "1_1") (pintype "passive"))
      (node (ref "C_AVCC1") (pin "2") (pinfunction "2_2") (pintype "passive"))
      (node (ref "R10") (pin "1") (pinfunction "1_1") (pintype "passive"))
      (node (ref "R6") (pin "1") (pinfunction "1_1") (pintype "passive"))
      (node (ref "R8") (pin "1") (pinfunction "1_1") (pintype "passive"))
      (node (ref "R_AGND") (pin "1") (pinfunction "1_1") (pintype "passive"))
      (node (ref "U$2") (pin "3") (pinfunction "GND_3") (pintype "passive"))
      (node (ref "U1") (pin "33") (pinfunction "GNDANA_33") (pintype "passive"))
    )
    (net (code "38") (name "GND") (class "Default")
      (node (ref "C1") (pin "2") (pinfunction "2_2") (pintype "passive"))
      (node (ref "C2") (pin "2") (pinfunction "2_2") (pintype "passive"))
      (node (ref "C3") (pin "2") (pinfunction "2_2") (pintype "passive"))
      (node (ref "C4") (pin "2") (pinfunction "2_2") (pintype "passive"))
      (node (ref "C5") (pin "2") (pinfunction "2_2") (pintype "passive"))
      (node (ref "C6") (pin "2") (pinfunction "2_2") (pintype "passive"))
      (node (ref "C7") (pin "-") (pinfunction "-_-") (pintype "passive"))
      (node (ref "C8") (pin "2") (pinfunction "2_2") (pintype "passive"))
      (node (ref "C_AUX_MOT1") (pin "2") (pinfunction "2_2") (pintype "passive"))
      (node (ref "C_AUX_MOT2") (pin "2") (pinfunction "2_2") (pintype "passive"))
      (node (ref "C_CORE") (pin "2") (pinfunction "2_2") (pintype "passive"))
      (node (ref "C_MCU_PWIN1") (pin "-") (pinfunction "-_-") (pintype "passive"))
      (node (ref "C_MCU_PWOUT") (pin "1") (pinfunction "1_1") (pintype "passive"))
      (node (ref "C_MCU_PWOUT1") (pin "-") (pinfunction "-_-") (pintype "passive"))
      (node (ref "C_MCU_PWOUT2") (pin "-") (pinfunction "-_-") (pintype "passive"))
      (node (ref "C_MCU_PW_IN") (pin "1") (pinfunction "1_1") (pintype "passive"))
      (node (ref "C_MOT_I1") (pin "1") (pinfunction "1_1") (pintype "passive"))
      (node (ref "C_MOT_I2") (pin "1") (pinfunction "1_1") (pintype "passive"))
      (node (ref "C_MPWR_DEBOUNCE") (pin "2") (pinfunction "2_2") (pintype "passive"))
      (node (ref "C_OUT_1") (pin "-") (pinfunction "-_-") (pintype "passive"))
      (node (ref "C_OUT_4") (pin "-") (pinfunction "-_-") (pintype "passive"))
      (node (ref "C_UART1") (pin "1") (pinfunction "1_1") (pintype "passive"))
      (node (ref "C_UART2") (pin "1") (pinfunction "1_1") (pintype "passive"))
      (node (ref "C_XTAL1") (pin "2") (pinfunction "2_2") (pintype "passive"))
      (node (ref "C_XTAL2") (pin "1") (pinfunction "1_1") (pintype "passive"))
      (node (ref "D12") (pin "A") (pinfunction "A_A") (pintype "passive"))
      (node (ref "D13") (pin "A") (pinfunction "A_A") (pintype "passive"))
      (node (ref "D14") (pin "A") (pinfunction "A_A") (pintype "passive"))
      (node (ref "D16") (pin "A") (pinfunction "A_A") (pintype "passive"))
      (node (ref "D2") (pin "A") (pinfunction "A_A") (pintype "passive"))
      (node (ref "D4") (pin "A") (pinfunction "A_A") (pintype "passive"))
      (node (ref "D6") (pin "A") (pinfunction "A_A") (pintype "passive"))
      (node (ref "D8") (pin "A") (pinfunction "A_A") (pintype "passive"))
      (node (ref "EXT_REG") (pin "2") (pinfunction "2_2") (pintype "passive"))
      (node (ref "GND_BRACE1") (pin "1") (pinfunction "1_1") (pintype "passive"))
      (node (ref "GND_BRACE1") (pin "2") (pinfunction "2_2") (pintype "passive"))
      (node (ref "GND_BRACE2") (pin "1") (pinfunction "1_1") (pintype "passive"))
      (node (ref "GND_BRACE2") (pin "2") (pinfunction "2_2") (pintype "passive"))
      (node (ref "GND_BRACE3") (pin "1") (pinfunction "1_1") (pintype "passive"))
      (node (ref "GND_BRACE3") (pin "2") (pinfunction "2_2") (pintype "passive"))
      (node (ref "GND_BRACE4") (pin "1") (pinfunction "1_1") (pintype "passive"))
      (node (ref "GND_BRACE4") (pin "2") (pinfunction "2_2") (pintype "passive"))
      (node (ref "IC2") (pin "1") (pinfunction "ADJ_1") (pintype "input"))
      (node (ref "IC6") (pin "13") (pinfunction "ENA_13") (pintype "input"))
      (node (ref "IC6") (pin "8") (pinfunction "VSS_8") (pintype "power_in"))
      (node (ref "J1") (pin "4") (pinfunction "4_4") (pintype "bidirectional"))
      (node (ref "JP16") (pin "1") (pinfunction "1_1") (pintype "passive"))
      (node (ref "JP2") (pin "4") (pinfunction "4_4") (pintype "passive"))
      (node (ref "JP4") (pin "1") (pinfunction "1_1") (pintype "passive"))
      (node (ref "JP6") (pin "1") (pinfunction "1_1") (pintype "passive"))
      (node (ref "JP8") (pin "1") (pinfunction "1_1") (pintype "passive"))
      (node (ref "JP8") (pin "2") (pinfunction "2_2") (pintype "passive"))
      (node (ref "JP9") (pin "1") (pinfunction "1_1") (pintype "passive"))
      (node (ref "R_3V3_DRAIN") (pin "1") (pinfunction "1_1") (pintype "passive"))
      (node (ref "R_AGND") (pin "2") (pinfunction "2_2") (pintype "passive"))
      (node (ref "R_DEBUG1") (pin "1") (pinfunction "1_1") (pintype "passive"))
      (node (ref "R_DEBUG2") (pin "1") (pinfunction "1_1") (pintype "passive"))
      (node (ref "R_P3V3") (pin "1") (pinfunction "1_1") (pintype "passive"))
      (node (ref "R_P5V") (pin "1") (pinfunction "1_1") (pintype "passive"))
      (node (ref "R_PD_MOT_ENABLE") (pin "1") (pinfunction "1_1") (pintype "passive"))
      (node (ref "R_PWR_D") (pin "2") (pinfunction "2_2") (pintype "passive"))
      (node (ref "R_P_BATT") (pin "1") (pinfunction "1_1") (pintype "passive"))
      (node (ref "R_P_EXT") (pin "1") (pinfunction "1_1") (pintype "passive"))
      (node (ref "R_P_MOT") (pin "1") (pinfunction "1_1") (pintype "passive"))
      (node (ref "SV1") (pin "5") (pinfunction "5_5") (pintype "passive"))
      (node (ref "SV1") (pin "6") (pinfunction "6_6") (pintype "passive"))
      (node (ref "SV2") (pin "2") (pinfunction "2_2") (pintype "passive"))
      (node (ref "SV3") (pin "5") (pinfunction "5_5") (pintype "passive"))
      (node (ref "SV3") (pin "6") (pinfunction "6_6") (pintype "passive"))
      (node (ref "SV4") (pin "5") (pinfunction "5_5") (pintype "passive"))
      (node (ref "SV4") (pin "6") (pinfunction "6_6") (pintype "passive"))
      (node (ref "SV5") (pin "5") (pinfunction "5_5") (pintype "passive"))
      (node (ref "SV5") (pin "6") (pinfunction "6_6") (pintype "passive"))
      (node (ref "SV_EXT_UART") (pin "4") (pinfunction "4_4") (pintype "passive"))
      (node (ref "SV_JTAG") (pin "10") (pinfunction "10_10") (pintype "passive"))
      (node (ref "SV_JTAG") (pin "2") (pinfunction "2_2") (pintype "passive"))
      (node (ref "U$1") (pin "2") (pinfunction "GND_2") (pintype "bidirectional"))
      (node (ref "U$14") (pin "4") (pinfunction "GND_4") (pintype "bidirectional"))
      (node (ref "U$15") (pin "4") (pinfunction "GND_4") (pintype "bidirectional"))
      (node (ref "U$3") (pin "P$6") (pinfunction "GND_P$6") (pintype "bidirectional"))
      (node (ref "U$4") (pin "2") (pinfunction "VSS_2") (pintype "bidirectional"))
      (node (ref "U$4") (pin "5") (pinfunction "WP_5") (pintype "bidirectional"))
      (node (ref "U1") (pin "1") (pinfunction "GND_4_1") (pintype "passive"))
      (node (ref "U1") (pin "19") (pinfunction "GND_2_19") (pintype "passive"))
      (node (ref "U1") (pin "43") (pinfunction "GND_43") (pintype "passive"))
      (node (ref "U1") (pin "45") (pinfunction "GND_3_45") (pintype "passive"))
      (node (ref "U2") (pin "1") (pinfunction "CSA_1") (pintype "bidirectional"))
      (node (ref "U2") (pin "15") (pinfunction "CSB_15") (pintype "bidirectional"))
      (node (ref "U2") (pin "8") (pinfunction "GND_8") (pintype "bidirectional"))
    )
    (net (code "39") (name "Net-(C5-Pad1)") (class "Default")
      (node (ref "C5") (pin "1") (pinfunction "1_1") (pintype "passive"))
      (node (ref "C6") (pin "1") (pinfunction "1_1") (pintype "passive"))
      (node (ref "R14") (pin "1") (pinfunction "1_1") (pintype "passive"))
    )
    (net (code "40") (name "Net-(F2-Pad1A)") (class "Default")
      (node (ref "F2") (pin "1A") (pinfunction "1A_1A") (pintype "passive"))
      (node (ref "JP4") (pin "2") (pinfunction "2_2") (pintype "passive"))
    )
    (net (code "41") (name "Net-(IC6A-CLK)") (class "Default")
      (node (ref "IC6") (pin "14") (pinfunction "CLK_14") (pintype "input"))
      (node (ref "R_SERVO1") (pin "2") (pinfunction "2_2") (pintype "passive"))
      (node (ref "U$15") (pin "1") (pinfunction "OUT1_1") (pintype "bidirectional"))
    )
    (net (code "42") (name "Net-(IC6A-Q1)") (class "Default")
      (node (ref "IC6") (pin "2") (pinfunction "Q1_2") (pintype "output"))
      (node (ref "SV5") (pin "2") (pinfunction "2_2") (pintype "passive"))
    )
    (net (code "43") (name "Net-(IC6A-Q2)") (class "Default")
      (node (ref "IC6") (pin "4") (pinfunction "Q2_4") (pintype "output"))
      (node (ref "SV4") (pin "1") (pinfunction "1_1") (pintype "passive"))
    )
    (net (code "44") (name "Net-(IC6A-Q3)") (class "Default")
      (node (ref "IC6") (pin "7") (pinfunction "Q3_7") (pintype "output"))
      (node (ref "SV3") (pin "2") (pinfunction "2_2") (pintype "passive"))
    )
    (net (code "45") (name "Net-(IC6A-Q4)") (class "Default")
      (node (ref "IC6") (pin "10") (pinfunction "Q4_10") (pintype "output"))
      (node (ref "SV1") (pin "1") (pinfunction "1_1") (pintype "passive"))
    )
    (net (code "46") (name "Net-(IC6A-Q5)") (class "Default")
      (node (ref "IC6") (pin "1") (pinfunction "Q5_1") (pintype "output"))
      (node (ref "SV5") (pin "1") (pinfunction "1_1") (pintype "passive"))
    )
    (net (code "47") (name "Net-(IC6A-Q6)") (class "Default")
      (node (ref "IC6") (pin "5") (pinfunction "Q6_5") (pintype "output"))
      (node (ref "SV4") (pin "2") (pinfunction "2_2") (pintype "passive"))
    )
    (net (code "48") (name "Net-(IC6A-Q7)") (class "Default")
      (node (ref "IC6") (pin "6") (pinfunction "Q7_6") (pintype "output"))
      (node (ref "SV3") (pin "1") (pinfunction "1_1") (pintype "passive"))
    )
    (net (code "49") (name "Net-(IC6A-Q8)") (class "Default")
      (node (ref "IC6") (pin "9") (pinfunction "Q8_9") (pintype "output"))
      (node (ref "SV1") (pin "2") (pinfunction "2_2") (pintype "passive"))
    )
    (net (code "50") (name "Net-(IC6A-RES)") (class "Default")
      (node (ref "IC6") (pin "15") (pinfunction "RES_15") (pintype "input"))
      (node (ref "R_SERVO2") (pin "2") (pinfunction "2_2") (pintype "passive"))
      (node (ref "U$15") (pin "2") (pinfunction "OUT2_2") (pintype "bidirectional"))
    )
    (net (code "51") (name "Net-(JP2-Pad2)") (class "Default")
      (node (ref "JP2") (pin "2") (pinfunction "2_2") (pintype "passive"))
      (node (ref "R1") (pin "2") (pinfunction "2_2") (pintype "passive"))
    )
    (net (code "52") (name "Net-(JP2-Pad3)") (class "Default")
      (node (ref "JP2") (pin "3") (pinfunction "3_3") (pintype "passive"))
      (node (ref "R11") (pin "2") (pinfunction "2_2") (pintype "passive"))
    )
    (net (code "53") (name "Net-(LED1-PadC)") (class "Default")
      (node (ref "LED1") (pin "C") (pinfunction "C_C") (pintype "passive"))
      (node (ref "R_DEBUG1") (pin "2") (pinfunction "2_2") (pintype "passive"))
    )
    (net (code "54") (name "Net-(LED2-PadC)") (class "Default")
      (node (ref "LED2") (pin "C") (pinfunction "C_C") (pintype "passive"))
      (node (ref "R_DEBUG2") (pin "2") (pinfunction "2_2") (pintype "passive"))
    )
    (net (code "55") (name "Net-(LED_3V3-PadC)") (class "Default")
      (node (ref "LED_3V3") (pin "C") (pinfunction "C_C") (pintype "passive"))
      (node (ref "R_P3V3") (pin "2") (pinfunction "2_2") (pintype "passive"))
    )
    (net (code "56") (name "Net-(LED_5V_SERVO-PadC)") (class "Default")
      (node (ref "LED_5V_SERVO") (pin "C") (pinfunction "C_C") (pintype "passive"))
      (node (ref "R_P5V") (pin "2") (pinfunction "2_2") (pintype "passive"))
    )
    (net (code "57") (name "Net-(LED_PWR_BATT-PadC)") (class "Default")
      (node (ref "LED_PWR_BATT") (pin "C") (pinfunction "C_C") (pintype "passive"))
      (node (ref "R_P_BATT") (pin "2") (pinfunction "2_2") (pintype "passive"))
    )
    (net (code "58") (name "Net-(LED_PWR_EXT-PadC)") (class "Default")
      (node (ref "LED_PWR_EXT") (pin "C") (pinfunction "C_C") (pintype "passive"))
      (node (ref "R_P_EXT") (pin "2") (pinfunction "2_2") (pintype "passive"))
    )
    (net (code "59") (name "Net-(LED_PWR_MOT-PadC)") (class "Default")
      (node (ref "LED_PWR_MOT") (pin "C") (pinfunction "C_C") (pintype "passive"))
      (node (ref "R_P_MOT") (pin "2") (pinfunction "2_2") (pintype "passive"))
    )
    (net (code "60") (name "Net-(R2-Pad2)") (class "Default")
      (node (ref "R2") (pin "2") (pinfunction "2_2") (pintype "passive"))
      (node (ref "SV_EXT_UART") (pin "2") (pinfunction "2_2") (pintype "passive"))
    )
    (net (code "61") (name "Net-(R3-Pad2)") (class "Default")
      (node (ref "R3") (pin "2") (pinfunction "2_2") (pintype "passive"))
      (node (ref "SV_EXT_UART") (pin "3") (pinfunction "3_3") (pintype "passive"))
    )
    (net (code "62") (name "Net-(R15B-1)") (class "Default")
      (node (ref "R15") (pin "2") (pinfunction "1_2") (pintype "passive"))
      (node (ref "U1") (pin "26") (pinfunction "PA13_26") (pintype "bidirectional"))
    )
    (net (code "63") (name "Net-(R15C-1)") (class "Default")
      (node (ref "R15") (pin "4") (pinfunction "1_4") (pintype "passive"))
      (node (ref "U1") (pin "21") (pinfunction "PB04_21") (pintype "bidirectional"))
    )
    (net (code "64") (name "Net-(R15D-1)") (class "Default")
      (node (ref "R15") (pin "3") (pinfunction "1_3") (pintype "passive"))
      (node (ref "U1") (pin "25") (pinfunction "PA20_25") (pintype "bidirectional"))
    )
    (net (code "65") (name "Net-(R_MOT_INB-1)") (class "Default")
      (node (ref "R_MOT_IN") (pin "2") (pinfunction "1_2") (pintype "passive"))
      (node (ref "U1") (pin "8") (pinfunction "PB03_8") (pintype "bidirectional"))
    )
    (net (code "66") (name "Net-(R_MOT_INC-1)") (class "Default")
      (node (ref "R_MOT_IN") (pin "4") (pinfunction "1_4") (pintype "passive"))
      (node (ref "U1") (pin "6") (pinfunction "PB00_6") (pintype "bidirectional"))
    )
    (net (code "67") (name "Net-(R_MOT_IND-1)") (class "Default")
      (node (ref "R_MOT_IN") (pin "3") (pinfunction "1_3") (pintype "passive"))
      (node (ref "U1") (pin "12") (pinfunction "PA05_12") (pintype "bidirectional"))
    )
    (net (code "68") (name "Net-(U$1-VP)") (class "Default")
      (node (ref "Q2") (pin "5") (pinfunction "D_5") (pintype "passive"))
      (node (ref "Q2") (pin "6") (pinfunction "D_6") (pintype "passive"))
      (node (ref "Q2") (pin "7") (pinfunction "D_7") (pintype "passive"))
      (node (ref "Q2") (pin "8") (pinfunction "D_8") (pintype "passive"))
      (node (ref "R4") (pin "1") (pinfunction "1_1") (pintype "passive"))
      (node (ref "U$1") (pin "4") (pinfunction "VP_4") (pintype "bidirectional"))
    )
    (net (code "69") (name "Net-(U$2-VOUT)") (class "Default")
      (node (ref "R9") (pin "1") (pinfunction "1_1") (pintype "passive"))
      (node (ref "U$2") (pin "2") (pinfunction "VOUT_2") (pintype "output"))
    )
    (net (code "70") (name "Net-(U$3-OUT1)") (class "Default")
      (node (ref "D7") (pin "A") (pinfunction "A_A") (pintype "passive"))
      (node (ref "D8") (pin "C") (pinfunction "C_C") (pintype "passive"))
      (node (ref "JP7") (pin "1") (pinfunction "1_1") (pintype "passive"))
      (node (ref "U$3") (pin "P$10") (pinfunction "OUT1_P$10") (pintype "bidirectional"))
    )
    (net (code "71") (name "Net-(U$3-OUT2)") (class "Default")
      (node (ref "D5") (pin "A") (pinfunction "A_A") (pintype "passive"))
      (node (ref "D6") (pin "C") (pinfunction "C_C") (pintype "passive"))
      (node (ref "JP7") (pin "2") (pinfunction "2_2") (pintype "passive"))
      (node (ref "U$3") (pin "P$9") (pinfunction "OUT2_P$9") (pintype "bidirectional"))
    )
    (net (code "72") (name "Net-(U$3-OUT3)") (class "Default")
      (node (ref "D3") (pin "A") (pinfunction "A_A") (pintype "passive"))
      (node (ref "D4") (pin "C") (pinfunction "C_C") (pintype "passive"))
      (node (ref "JP7") (pin "3") (pinfunction "3_3") (pintype "passive"))
      (node (ref "U$3") (pin "P$8") (pinfunction "OUT3_P$8") (pintype "bidirectional"))
    )
    (net (code "73") (name "Net-(U$3-OUT4)") (class "Default")
      (node (ref "D1") (pin "A") (pinfunction "A_A") (pintype "passive"))
      (node (ref "D2") (pin "C") (pinfunction "C_C") (pintype "passive"))
      (node (ref "JP7") (pin "4") (pinfunction "4_4") (pintype "passive"))
      (node (ref "U$3") (pin "P$7") (pinfunction "OUT4_P$7") (pintype "bidirectional"))
    )
    (net (code "74") (name "Net-(U$4-VCC)") (class "Default")
      (node (ref "J1") (pin "3") (pinfunction "3_3") (pintype "bidirectional"))
      (node (ref "R12") (pin "2") (pinfunction "2_2") (pintype "passive"))
      (node (ref "R13") (pin "2") (pinfunction "2_2") (pintype "passive"))
      (node (ref "U$4") (pin "4") (pinfunction "VCC_4") (pintype "bidirectional"))
      (node (ref "V_SEL1") (pin "1") (pinfunction "1_1") (pintype "passive"))
      (node (ref "V_SEL2") (pin "1") (pinfunction "1_1") (pintype "passive"))
    )
    (net (code "75") (name "Net-(U$14-OUT1)") (class "Default")
      (node (ref "JP15") (pin "1") (pinfunction "1_1") (pintype "passive"))
      (node (ref "U$14") (pin "1") (pinfunction "OUT1_1") (pintype "bidirectional"))
    )
    (net (code "76") (name "Net-(U$14-OUT2)") (class "Default")
      (node (ref "R_PWR_FET1") (pin "2") (pinfunction "2_2") (pintype "passive"))
      (node (ref "U$14") (pin "2") (pinfunction "OUT2_2") (pintype "bidirectional"))
    )
    (net (code "77") (name "Net-(U1-ADVREFP)") (class "Default")
      (node (ref "C_AVCC") (pin "2") (pinfunction "2_2") (pintype "passive"))
      (node (ref "R_ANA") (pin "2") (pinfunction "2_2") (pintype "passive"))
      (node (ref "U1") (pin "34") (pinfunction "ADVREFP_34") (pintype "input"))
      (node (ref "U1") (pin "35") (pinfunction "VDDANA_35") (pintype "power_in"))
    )
    (net (code "78") (name "Net-(U1-PA11)") (class "Default")
      (node (ref "R15") (pin "1") (pinfunction "1_1") (pintype "passive"))
      (node (ref "U1") (pin "27") (pinfunction "PA11_27") (pintype "bidirectional"))
    )
    (net (code "79") (name "Net-(U1-PA14)") (class "Default")
      (node (ref "C_ASIG1") (pin "1") (pinfunction "1_1") (pintype "passive"))
      (node (ref "R7") (pin "1") (pinfunction "1_1") (pintype "passive"))
      (node (ref "R8") (pin "2") (pinfunction "2_2") (pintype "passive"))
      (node (ref "U1") (pin "36") (pinfunction "PA14_36") (pintype "bidirectional"))
    )
    (net (code "80") (name "Net-(U1-PA15)") (class "Default")
      (node (ref "C_ASIG2") (pin "1") (pinfunction "1_1") (pintype "passive"))
      (node (ref "R5") (pin "1") (pinfunction "1_1") (pintype "passive"))
      (node (ref "R6") (pin "2") (pinfunction "2_2") (pintype "passive"))
      (node (ref "U1") (pin "37") (pinfunction "PA15_37") (pintype "bidirectional"))
    )
    (net (code "81") (name "Net-(U1-PA16)") (class "Default")
      (node (ref "C_ASIG3") (pin "1") (pinfunction "1_1") (pintype "passive"))
      (node (ref "R10") (pin "2") (pinfunction "2_2") (pintype "passive"))
      (node (ref "R9") (pin "2") (pinfunction "2_2") (pintype "passive"))
      (node (ref "U1") (pin "38") (pinfunction "PA16_38") (pintype "bidirectional"))
    )
    (net (code "82") (name "Net-(U1-PA22)") (class "Default")
      (node (ref "R_MOT_IN") (pin "1") (pinfunction "1_1") (pintype "passive"))
      (node (ref "U1") (pin "9") (pinfunction "PA22_9") (pintype "bidirectional"))
    )
    (net (code "83") (name "Net-(U1-PB02)") (class "Default")
      (node (ref "R_MOT_ENABLE") (pin "1") (pinfunction "1_1") (pintype "passive"))
      (node (ref "U1") (pin "7") (pinfunction "PB02_7") (pintype "bidirectional"))
    )
    (net (code "84") (name "Net-(U1-PB10)") (class "Default")
      (node (ref "JP3") (pin "1") (pinfunction "1_1") (pintype "passive"))
      (node (ref "U1") (pin "23") (pinfunction "PB10_23") (pintype "bidirectional"))
    )
    (net (code "85") (name "Net-(U1-VDDCORE)") (class "Default")
      (node (ref "C_CORE") (pin "1") (pinfunction "1_1") (pintype "passive"))
      (node (ref "R14") (pin "2") (pinfunction "2_2") (pintype "passive"))
      (node (ref "R_ANA") (pin "1") (pinfunction "1_1") (pintype "passive"))
      (node (ref "U1") (pin "18") (pinfunction "VDDCORE_18") (pintype "power_in"))
    )
    (net (code "86") (name "Net-(U2-OUT1)") (class "Default")
      (node (ref "D14") (pin "C") (pinfunction "C_C") (pintype "passive"))
      (node (ref "D9") (pin "A") (pinfunction "A_A") (pintype "passive"))
      (node (ref "JP10") (pin "1") (pinfunction "1_1") (pintype "passive"))
      (node (ref "U2") (pin "2") (pinfunction "OUT1_2") (pintype "bidirectional"))
    )
    (net (code "87") (name "Net-(U2-OUT2)") (class "Default")
      (node (ref "D15") (pin "A") (pinfunction "A_A") (pintype "passive"))
      (node (ref "D16") (pin "C") (pinfunction "C_C") (pintype "passive"))
      (node (ref "JP11") (pin "1") (pinfunction "1_1") (pintype "passive"))
      (node (ref "U2") (pin "3") (pinfunction "OUT2_3") (pintype "bidirectional"))
    )
    (net (code "88") (name "Net-(U2-OUT3)") (class "Default")
      (node (ref "D10") (pin "A") (pinfunction "A_A") (pintype "passive"))
      (node (ref "D13") (pin "C") (pinfunction "C_C") (pintype "passive"))
      (node (ref "JP12") (pin "1") (pinfunction "1_1") (pintype "passive"))
      (node (ref "U2") (pin "13") (pinfunction "OUT3_13") (pintype "bidirectional"))
    )
    (net (code "89") (name "Net-(U2-OUT4)") (class "Default")
      (node (ref "D11") (pin "A") (pinfunction "A_A") (pintype "passive"))
      (node (ref "D12") (pin "C") (pinfunction "C_C") (pintype "passive"))
      (node (ref "JP13") (pin "1") (pinfunction "1_1") (pintype "passive"))
      (node (ref "U2") (pin "14") (pinfunction "OUT4_14") (pintype "bidirectional"))
    )
    (net (code "90") (name "unconnected-(F2-Pad1B)") (class "Default")
      (node (ref "F2") (pin "1B") (pinfunction "1B_1B") (pintype "passive"))
    )
    (net (code "91") (name "unconnected-(F2-Pad2B)") (class "Default")
      (node (ref "F2") (pin "2B") (pinfunction "2B_2B") (pintype "passive"))
    )
    (net (code "92") (name "unconnected-(IC6A-CO-Pad12)") (class "Default")
      (node (ref "IC6") (pin "12") (pinfunction "CO_12") (pintype "output"))
    )
    (net (code "93") (name "unconnected-(IC6A-Q0-Pad3)") (class "Default")
      (node (ref "IC6") (pin "3") (pinfunction "Q0_3") (pintype "output"))
    )
    (net (code "94") (name "unconnected-(IC6A-Q9-Pad11)") (class "Default")
      (node (ref "IC6") (pin "11") (pinfunction "Q9_11") (pintype "output"))
    )
    (net (code "95") (name "unconnected-(JP5-1-PadP$1)") (class "Default")
      (node (ref "JP5") (pin "P$1") (pinfunction "1_P$1") (pintype "passive"))
    )
    (net (code "96") (name "unconnected-(JP5-2-PadP$2)") (class "Default")
      (node (ref "JP5") (pin "P$2") (pinfunction "2_P$2") (pintype "passive"))
    )
    (net (code "97") (name "unconnected-(JP14-Pad1)") (class "Default")
      (node (ref "JP14") (pin "1") (pinfunction "1_1") (pintype "passive"))
    )
    (net (code "98") (name "unconnected-(JP14-Pad2)") (class "Default")
      (node (ref "JP14") (pin "2") (pinfunction "2_2") (pintype "passive"))
    )
    (net (code "99") (name "unconnected-(SV_JTAG-Pad7)") (class "Default")
      (node (ref "SV_JTAG") (pin "7") (pinfunction "7_7") (pintype "passive"))
    )
    (net (code "100") (name "unconnected-(SV_JTAG-Pad8)") (class "Default")
      (node (ref "SV_JTAG") (pin "8") (pinfunction "8_8") (pintype "passive"))
    )
    (net (code "101") (name "unconnected-(U1-PA18-Pad41)") (class "Default")
      (node (ref "U1") (pin "41") (pinfunction "PA18_41") (pintype "bidirectional"))
    )
    (net (code "102") (name "unconnected-(U1-PB01-Pad16)") (class "Default")
      (node (ref "U1") (pin "16") (pinfunction "PB01_16") (pintype "bidirectional"))
    )
    (net (code "103") (name "unconnected-(U1-PB08-Pad32)") (class "Default")
      (node (ref "U1") (pin "32") (pinfunction "PB08_32") (pintype "bidirectional"))
    )
    (net (code "104") (name "unconnected-(U1-PB11-Pad44)") (class "Default")
      (node (ref "U1") (pin "44") (pinfunction "PB11_44") (pintype "bidirectional"))
    )
    (net (code "105") (name "unconnected-(U1-PB12-Pad5)") (class "Default")
      (node (ref "U1") (pin "5") (pinfunction "PB12_5") (pintype "bidirectional"))
    )
  )
)
